# RFMC_DAC.net
KiCad netlist of a schematic drawn in Altium Designer
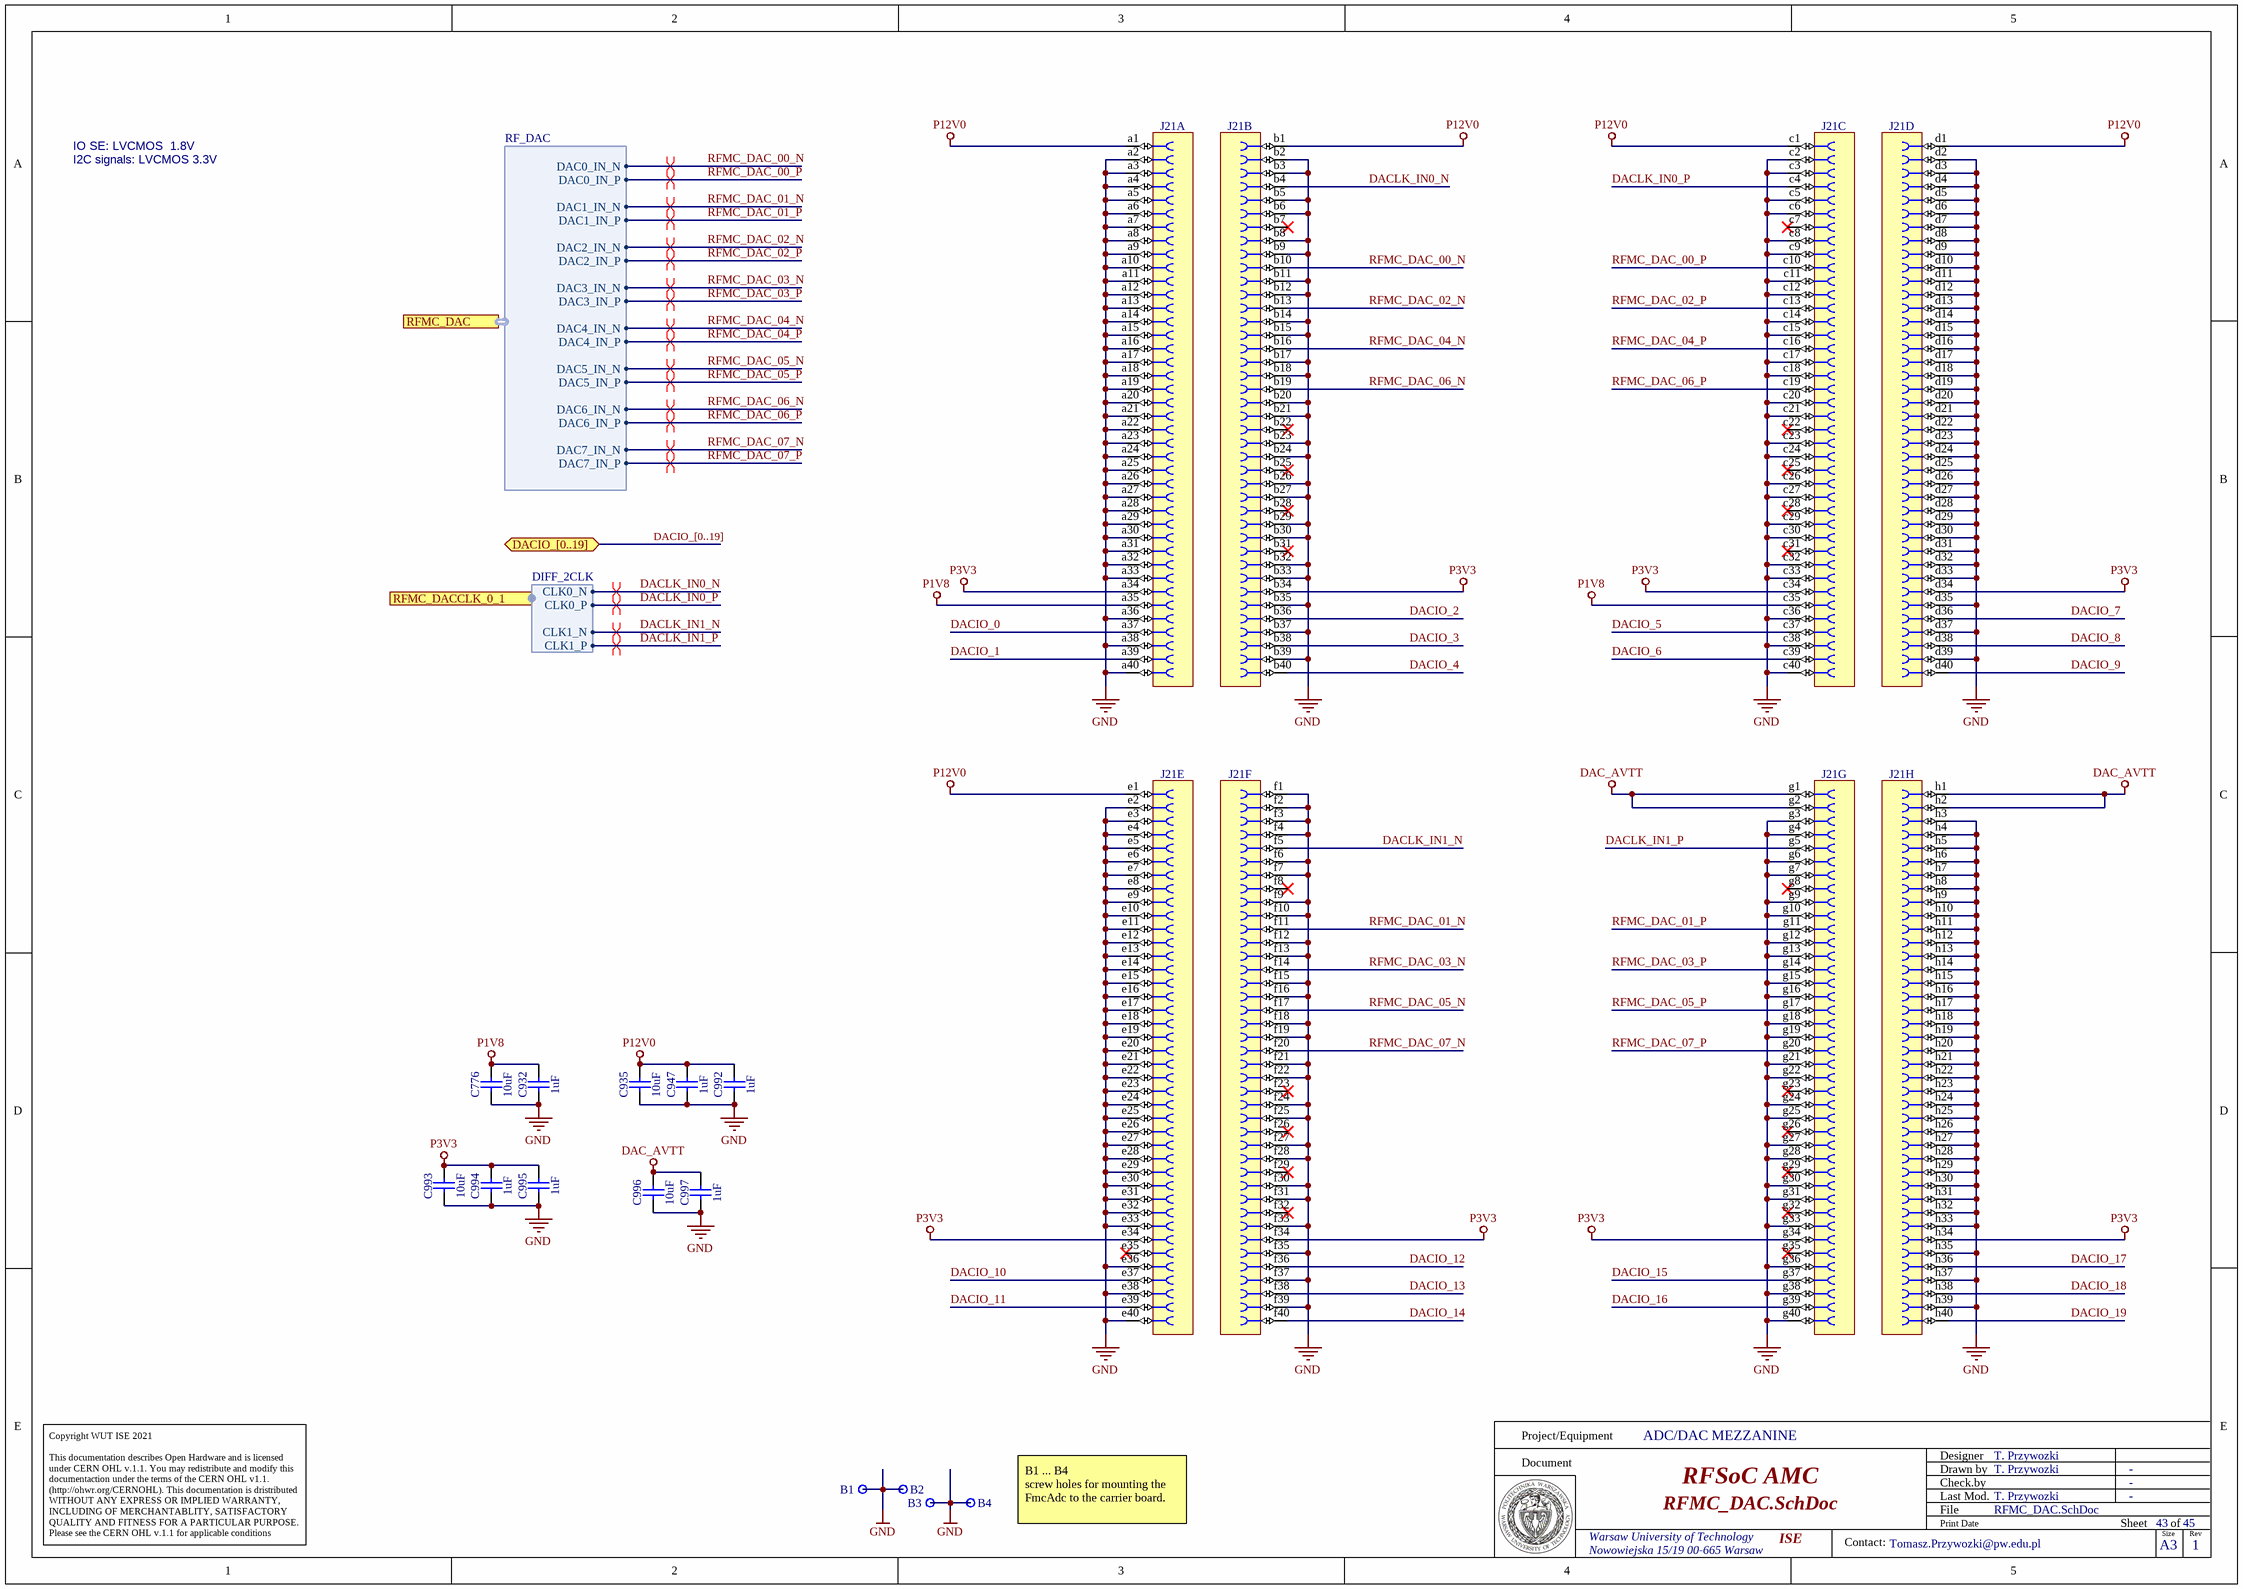
[diagram p0: RFMC_DAC.SchDoc]

(export (version "E")
  (design (tool "Eeschema 10.0.6"))
  (components
    (comp (ref "B1")
      (value "Plated Hole")
      (footprint "MTG270_500")
      (description "Single Terminal Socket")
      (fields (field (name "PART NUMBER") "PLATED_HOLE2.7_PAD5.0") (field (name "AUTHOR") "CERN DEM JMW"))
      (libsource (lib "Eletro-mechanical") (part "Single Terminal Socket"))
    )
    (comp (ref "B2")
      (value "Plated Hole")
      (footprint "MTG270_500")
      (description "Single Terminal Socket")
      (fields (field (name "PART NUMBER") "PLATED_HOLE2.7_PAD5.0") (field (name "AUTHOR") "CERN DEM JMW"))
      (libsource (lib "Eletro-mechanical") (part "Single Terminal Socket"))
    )
    (comp (ref "B3")
      (value "Plated Hole")
      (footprint "MTG270_500")
      (description "Single Terminal Socket")
      (fields (field (name "PART NUMBER") "PLATED_HOLE2.7_PAD5.0") (field (name "AUTHOR") "CERN DEM JMW"))
      (libsource (lib "Eletro-mechanical") (part "Single Terminal Socket"))
    )
    (comp (ref "B4")
      (value "Plated Hole")
      (footprint "MTG270_500")
      (description "Single Terminal Socket")
      (fields (field (name "PART NUMBER") "PLATED_HOLE2.7_PAD5.0") (field (name "AUTHOR") "CERN DEM JMW"))
      (libsource (lib "Eletro-mechanical") (part "Single Terminal Socket"))
    )
    (comp (ref "C776")
      (value "10uF")
      (footprint "CAPC1608X80N")
      (description "Non-polarised capacitor")
      (fields
        (field (name "PART NUMBER") "CC0603_10UF_10V_10%_X5R")
        (field (name "VOLTAGE") "10V")
        (field (name "AUTHOR") "CERN DEM JLC")
      )
      (libsource (lib "Capacitors") (part "Capacitor - non polarized"))
    )
    (comp (ref "C932")
      (value "1uF")
      (footprint "CAPC1005X55N")
      (description "Non-polarised capacitor")
      (fields
        (field (name "PART NUMBER") "CC0402_1UF_16V_10%_X5R")
        (field (name "VOLTAGE") "16V")
        (field (name "AUTHOR") "CERN DEM JLC")
      )
      (libsource (lib "Capacitors") (part "Capacitor - non polarized"))
    )
    (comp (ref "C935")
      (value "10uF")
      (footprint "CAPC1608X80N")
      (description "Non-polarised capacitor")
      (fields
        (field (name "PART NUMBER") "CC0603_10UF_10V_10%_X5R")
        (field (name "VOLTAGE") "10V")
        (field (name "AUTHOR") "CERN DEM JLC")
      )
      (libsource (lib "Capacitors") (part "Capacitor - non polarized"))
    )
    (comp (ref "C947")
      (value "1uF")
      (footprint "CAPC1005X55N")
      (description "Non-polarised capacitor")
      (fields
        (field (name "PART NUMBER") "CC0402_1UF_16V_10%_X5R")
        (field (name "VOLTAGE") "16V")
        (field (name "AUTHOR") "CERN DEM JLC")
      )
      (libsource (lib "Capacitors") (part "Capacitor - non polarized"))
    )
    (comp (ref "C992")
      (value "1uF")
      (footprint "CAPC1005X55N")
      (description "Non-polarised capacitor")
      (fields
        (field (name "PART NUMBER") "CC0402_1UF_16V_10%_X5R")
        (field (name "VOLTAGE") "16V")
        (field (name "AUTHOR") "CERN DEM JLC")
      )
      (libsource (lib "Capacitors") (part "Capacitor - non polarized"))
    )
    (comp (ref "C993")
      (value "10uF")
      (footprint "CAPC1608X80N")
      (description "Non-polarised capacitor")
      (fields
        (field (name "PART NUMBER") "CC0603_10UF_10V_10%_X5R")
        (field (name "VOLTAGE") "10V")
        (field (name "AUTHOR") "CERN DEM JLC")
      )
      (libsource (lib "Capacitors") (part "Capacitor - non polarized"))
    )
    (comp (ref "C994")
      (value "1uF")
      (footprint "CAPC1005X55N")
      (description "Non-polarised capacitor")
      (fields
        (field (name "PART NUMBER") "CC0402_1UF_16V_10%_X5R")
        (field (name "VOLTAGE") "16V")
        (field (name "AUTHOR") "CERN DEM JLC")
      )
      (libsource (lib "Capacitors") (part "Capacitor - non polarized"))
    )
    (comp (ref "C995")
      (value "1uF")
      (footprint "CAPC1005X55N")
      (description "Non-polarised capacitor")
      (fields
        (field (name "PART NUMBER") "CC0402_1UF_16V_10%_X5R")
        (field (name "VOLTAGE") "16V")
        (field (name "AUTHOR") "CERN DEM JLC")
      )
      (libsource (lib "Capacitors") (part "Capacitor - non polarized"))
    )
    (comp (ref "C996")
      (value "10uF")
      (footprint "CAPC1608X80N")
      (description "Non-polarised capacitor")
      (fields
        (field (name "PART NUMBER") "CC0603_10UF_10V_10%_X5R")
        (field (name "VOLTAGE") "10V")
        (field (name "AUTHOR") "CERN DEM JLC")
      )
      (libsource (lib "Capacitors") (part "Capacitor - non polarized"))
    )
    (comp (ref "C997")
      (value "1uF")
      (footprint "CAPC1005X55N")
      (description "Non-polarised capacitor")
      (fields
        (field (name "PART NUMBER") "CC0402_1UF_16V_10%_X5R")
        (field (name "VOLTAGE") "16V")
        (field (name "AUTHOR") "CERN DEM JLC")
      )
      (libsource (lib "Capacitors") (part "Capacitor - non polarized"))
    )
    (comp (ref "J21")
      (value "~")
      (footprint "SAMTEC_LPAF-40-03.0-S-08")
      (description "Connector 320 Female contacts in 8 row abcdef")
      (fields
        (field (name "PART NUMBER") "SAMTEC_LPAF-40-03.0-S-08-2-K")
        (field (name "MANUFACTURER") "SAMTEC")
        (field (name "AUTHOR") "CERN DEM BC")
      )
      (libsource (lib "Connectors") (part "Connector 320 Female (8x40) (abcdefgh)"))
    )
  )
  (nets
    (net (code "3") (name "/DACIO_0") (class "Default")
      (node (ref "J21") (pin "a37") (pinfunction "a37_a37") (pintype "bidirectional"))
    )
    (net (code "4") (name "/DACIO_1") (class "Default")
      (node (ref "J21") (pin "a39") (pinfunction "a39_a39") (pintype "bidirectional"))
    )
    (net (code "5") (name "/DACIO_2") (class "Default")
      (node (ref "J21") (pin "b36") (pinfunction "b36_b36") (pintype "bidirectional"))
    )
    (net (code "6") (name "/DACIO_3") (class "Default")
      (node (ref "J21") (pin "b38") (pinfunction "b38_b38") (pintype "bidirectional"))
    )
    (net (code "7") (name "/DACIO_4") (class "Default")
      (node (ref "J21") (pin "b40") (pinfunction "b40_b40") (pintype "bidirectional"))
    )
    (net (code "8") (name "/DACIO_5") (class "Default")
      (node (ref "J21") (pin "c37") (pinfunction "c37_c37") (pintype "bidirectional"))
    )
    (net (code "9") (name "/DACIO_6") (class "Default")
      (node (ref "J21") (pin "c39") (pinfunction "c39_c39") (pintype "bidirectional"))
    )
    (net (code "10") (name "/DACIO_7") (class "Default")
      (node (ref "J21") (pin "d36") (pinfunction "d36_d36") (pintype "bidirectional"))
    )
    (net (code "11") (name "/DACIO_8") (class "Default")
      (node (ref "J21") (pin "d38") (pinfunction "d38_d38") (pintype "bidirectional"))
    )
    (net (code "12") (name "/DACIO_9") (class "Default")
      (node (ref "J21") (pin "d40") (pinfunction "d40_d40") (pintype "bidirectional"))
    )
    (net (code "13") (name "/DACIO_10") (class "Default")
      (node (ref "J21") (pin "e37") (pinfunction "e37_e37") (pintype "bidirectional"))
    )
    (net (code "14") (name "/DACIO_11") (class "Default")
      (node (ref "J21") (pin "e39") (pinfunction "e39_e39") (pintype "bidirectional"))
    )
    (net (code "15") (name "/DACIO_12") (class "Default")
      (node (ref "J21") (pin "f36") (pinfunction "f36_f36") (pintype "bidirectional"))
    )
    (net (code "16") (name "/DACIO_13") (class "Default")
      (node (ref "J21") (pin "f38") (pinfunction "f38_f38") (pintype "bidirectional"))
    )
    (net (code "17") (name "/DACIO_14") (class "Default")
      (node (ref "J21") (pin "f40") (pinfunction "f40_f40") (pintype "bidirectional"))
    )
    (net (code "18") (name "/DACIO_15") (class "Default")
      (node (ref "J21") (pin "g37") (pinfunction "g37_g37") (pintype "bidirectional"))
    )
    (net (code "19") (name "/DACIO_16") (class "Default")
      (node (ref "J21") (pin "g39") (pinfunction "g39_g39") (pintype "bidirectional"))
    )
    (net (code "20") (name "/DACIO_17") (class "Default")
      (node (ref "J21") (pin "h36") (pinfunction "h36_h36") (pintype "bidirectional"))
    )
    (net (code "21") (name "/DACIO_18") (class "Default")
      (node (ref "J21") (pin "h38") (pinfunction "h38_h38") (pintype "bidirectional"))
    )
    (net (code "22") (name "/DACIO_19") (class "Default")
      (node (ref "J21") (pin "h40") (pinfunction "h40_h40") (pintype "bidirectional"))
    )
    (net (code "24") (name "/DACLK_IN0_N") (class "Default")
      (node (ref "J21") (pin "b4") (pinfunction "b4_b4") (pintype "bidirectional"))
    )
    (net (code "25") (name "/DACLK_IN0_P") (class "Default")
      (node (ref "J21") (pin "c4") (pinfunction "c4_c4") (pintype "bidirectional"))
    )
    (net (code "26") (name "/DACLK_IN1_N") (class "Default")
      (node (ref "J21") (pin "f5") (pinfunction "f5_f5") (pintype "bidirectional"))
    )
    (net (code "27") (name "/DACLK_IN1_P") (class "Default")
      (node (ref "J21") (pin "g5") (pinfunction "g5_g5") (pintype "bidirectional"))
    )
    (net (code "28") (name "/RFMC_DAC_00_N") (class "Default")
      (node (ref "J21") (pin "b10") (pinfunction "b10_b10") (pintype "bidirectional"))
    )
    (net (code "29") (name "/RFMC_DAC_00_P") (class "Default")
      (node (ref "J21") (pin "c10") (pinfunction "c10_c10") (pintype "bidirectional"))
    )
    (net (code "30") (name "/RFMC_DAC_01_N") (class "Default")
      (node (ref "J21") (pin "f11") (pinfunction "f11_f11") (pintype "bidirectional"))
    )
    (net (code "31") (name "/RFMC_DAC_01_P") (class "Default")
      (node (ref "J21") (pin "g11") (pinfunction "g11_g11") (pintype "bidirectional"))
    )
    (net (code "32") (name "/RFMC_DAC_02_N") (class "Default")
      (node (ref "J21") (pin "b13") (pinfunction "b13_b13") (pintype "bidirectional"))
    )
    (net (code "33") (name "/RFMC_DAC_02_P") (class "Default")
      (node (ref "J21") (pin "c13") (pinfunction "c13_c13") (pintype "bidirectional"))
    )
    (net (code "34") (name "/RFMC_DAC_03_N") (class "Default")
      (node (ref "J21") (pin "f14") (pinfunction "f14_f14") (pintype "bidirectional"))
    )
    (net (code "35") (name "/RFMC_DAC_03_P") (class "Default")
      (node (ref "J21") (pin "g14") (pinfunction "g14_g14") (pintype "bidirectional"))
    )
    (net (code "36") (name "/RFMC_DAC_04_N") (class "Default")
      (node (ref "J21") (pin "b16") (pinfunction "b16_b16") (pintype "bidirectional"))
    )
    (net (code "37") (name "/RFMC_DAC_04_P") (class "Default")
      (node (ref "J21") (pin "c16") (pinfunction "c16_c16") (pintype "bidirectional"))
    )
    (net (code "38") (name "/RFMC_DAC_05_N") (class "Default")
      (node (ref "J21") (pin "f17") (pinfunction "f17_f17") (pintype "bidirectional"))
    )
    (net (code "39") (name "/RFMC_DAC_05_P") (class "Default")
      (node (ref "J21") (pin "g17") (pinfunction "g17_g17") (pintype "bidirectional"))
    )
    (net (code "40") (name "/RFMC_DAC_06_N") (class "Default")
      (node (ref "J21") (pin "b19") (pinfunction "b19_b19") (pintype "bidirectional"))
    )
    (net (code "41") (name "/RFMC_DAC_06_P") (class "Default")
      (node (ref "J21") (pin "c19") (pinfunction "c19_c19") (pintype "bidirectional"))
    )
    (net (code "42") (name "/RFMC_DAC_07_N") (class "Default")
      (node (ref "J21") (pin "f20") (pinfunction "f20_f20") (pintype "bidirectional"))
    )
    (net (code "43") (name "/RFMC_DAC_07_P") (class "Default")
      (node (ref "J21") (pin "g20") (pinfunction "g20_g20") (pintype "bidirectional"))
    )
    (net (code "46") (name "DAC_AVTT") (class "Default")
      (node (ref "C996") (pin "2") (pinfunction "2_2") (pintype "passive"))
      (node (ref "C997") (pin "1") (pinfunction "1_1") (pintype "passive"))
      (node (ref "J21") (pin "g1") (pinfunction "g1_g1") (pintype "bidirectional"))
      (node (ref "J21") (pin "g2") (pinfunction "g2_g2") (pintype "bidirectional"))
      (node (ref "J21") (pin "h1") (pinfunction "h1_h1") (pintype "bidirectional"))
      (node (ref "J21") (pin "h2") (pinfunction "h2_h2") (pintype "bidirectional"))
    )
    (net (code "47") (name "GND") (class "Default")
      (node (ref "B1") (pin "1") (pinfunction "1_1") (pintype "bidirectional"))
      (node (ref "B2") (pin "1") (pinfunction "1_1") (pintype "bidirectional"))
      (node (ref "B3") (pin "1") (pinfunction "1_1") (pintype "bidirectional"))
      (node (ref "B4") (pin "1") (pinfunction "1_1") (pintype "bidirectional"))
      (node (ref "C776") (pin "1") (pinfunction "1_1") (pintype "passive"))
      (node (ref "C932") (pin "2") (pinfunction "2_2") (pintype "passive"))
      (node (ref "C935") (pin "1") (pinfunction "1_1") (pintype "passive"))
      (node (ref "C947") (pin "2") (pinfunction "2_2") (pintype "passive"))
      (node (ref "C992") (pin "2") (pinfunction "2_2") (pintype "passive"))
      (node (ref "C993") (pin "1") (pinfunction "1_1") (pintype "passive"))
      (node (ref "C994") (pin "2") (pinfunction "2_2") (pintype "passive"))
      (node (ref "C995") (pin "2") (pinfunction "2_2") (pintype "passive"))
      (node (ref "C996") (pin "1") (pinfunction "1_1") (pintype "passive"))
      (node (ref "C997") (pin "2") (pinfunction "2_2") (pintype "passive"))
      (node (ref "J21") (pin "a10") (pinfunction "a10_a10") (pintype "bidirectional"))
      (node (ref "J21") (pin "a11") (pinfunction "a11_a11") (pintype "bidirectional"))
      (node (ref "J21") (pin "a12") (pinfunction "a12_a12") (pintype "bidirectional"))
      (node (ref "J21") (pin "a13") (pinfunction "a13_a13") (pintype "bidirectional"))
      (node (ref "J21") (pin "a14") (pinfunction "a14_a14") (pintype "bidirectional"))
      (node (ref "J21") (pin "a15") (pinfunction "a15_a15") (pintype "bidirectional"))
      (node (ref "J21") (pin "a16") (pinfunction "a16_a16") (pintype "bidirectional"))
      (node (ref "J21") (pin "a17") (pinfunction "a17_a17") (pintype "bidirectional"))
      (node (ref "J21") (pin "a18") (pinfunction "a18_a18") (pintype "bidirectional"))
      (node (ref "J21") (pin "a19") (pinfunction "a19_a19") (pintype "bidirectional"))
      (node (ref "J21") (pin "a2") (pinfunction "a2_a2") (pintype "bidirectional"))
      (node (ref "J21") (pin "a20") (pinfunction "a20_a20") (pintype "bidirectional"))
      (node (ref "J21") (pin "a21") (pinfunction "a21_a21") (pintype "bidirectional"))
      (node (ref "J21") (pin "a22") (pinfunction "a22_a22") (pintype "bidirectional"))
      (node (ref "J21") (pin "a23") (pinfunction "a23_a23") (pintype "bidirectional"))
      (node (ref "J21") (pin "a24") (pinfunction "a24_a24") (pintype "bidirectional"))
      (node (ref "J21") (pin "a25") (pinfunction "a25_a25") (pintype "bidirectional"))
      (node (ref "J21") (pin "a26") (pinfunction "a26_a26") (pintype "bidirectional"))
      (node (ref "J21") (pin "a27") (pinfunction "a27_a27") (pintype "bidirectional"))
      (node (ref "J21") (pin "a28") (pinfunction "a28_a28") (pintype "bidirectional"))
      (node (ref "J21") (pin "a29") (pinfunction "a29_a29") (pintype "bidirectional"))
      (node (ref "J21") (pin "a3") (pinfunction "a3_a3") (pintype "bidirectional"))
      (node (ref "J21") (pin "a30") (pinfunction "a30_a30") (pintype "bidirectional"))
      (node (ref "J21") (pin "a31") (pinfunction "a31_a31") (pintype "bidirectional"))
      (node (ref "J21") (pin "a32") (pinfunction "a32_a32") (pintype "bidirectional"))
      (node (ref "J21") (pin "a33") (pinfunction "a33_a33") (pintype "bidirectional"))
      (node (ref "J21") (pin "a36") (pinfunction "a36_a36") (pintype "bidirectional"))
      (node (ref "J21") (pin "a38") (pinfunction "a38_a38") (pintype "bidirectional"))
      (node (ref "J21") (pin "a4") (pinfunction "a4_a4") (pintype "bidirectional"))
      (node (ref "J21") (pin "a40") (pinfunction "a40_a40") (pintype "bidirectional"))
      (node (ref "J21") (pin "a5") (pinfunction "a5_a5") (pintype "bidirectional"))
      (node (ref "J21") (pin "a6") (pinfunction "a6_a6") (pintype "bidirectional"))
      (node (ref "J21") (pin "a7") (pinfunction "a7_a7") (pintype "bidirectional"))
      (node (ref "J21") (pin "a8") (pinfunction "a8_a8") (pintype "bidirectional"))
      (node (ref "J21") (pin "a9") (pinfunction "a9_a9") (pintype "bidirectional"))
      (node (ref "J21") (pin "b11") (pinfunction "b11_b11") (pintype "bidirectional"))
      (node (ref "J21") (pin "b12") (pinfunction "b12_b12") (pintype "bidirectional"))
      (node (ref "J21") (pin "b14") (pinfunction "b14_b14") (pintype "bidirectional"))
      (node (ref "J21") (pin "b15") (pinfunction "b15_b15") (pintype "bidirectional"))
      (node (ref "J21") (pin "b17") (pinfunction "b17_b17") (pintype "bidirectional"))
      (node (ref "J21") (pin "b18") (pinfunction "b18_b18") (pintype "bidirectional"))
      (node (ref "J21") (pin "b2") (pinfunction "b2_b2") (pintype "bidirectional"))
      (node (ref "J21") (pin "b20") (pinfunction "b20_b20") (pintype "bidirectional"))
      (node (ref "J21") (pin "b21") (pinfunction "b21_b21") (pintype "bidirectional"))
      (node (ref "J21") (pin "b23") (pinfunction "b23_b23") (pintype "bidirectional"))
      (node (ref "J21") (pin "b24") (pinfunction "b24_b24") (pintype "bidirectional"))
      (node (ref "J21") (pin "b26") (pinfunction "b26_b26") (pintype "bidirectional"))
      (node (ref "J21") (pin "b27") (pinfunction "b27_b27") (pintype "bidirectional"))
      (node (ref "J21") (pin "b29") (pinfunction "b29_b29") (pintype "bidirectional"))
      (node (ref "J21") (pin "b3") (pinfunction "b3_b3") (pintype "bidirectional"))
      (node (ref "J21") (pin "b30") (pinfunction "b30_b30") (pintype "bidirectional"))
      (node (ref "J21") (pin "b32") (pinfunction "b32_b32") (pintype "bidirectional"))
      (node (ref "J21") (pin "b33") (pinfunction "b33_b33") (pintype "bidirectional"))
      (node (ref "J21") (pin "b35") (pinfunction "b35_b35") (pintype "bidirectional"))
      (node (ref "J21") (pin "b37") (pinfunction "b37_b37") (pintype "bidirectional"))
      (node (ref "J21") (pin "b39") (pinfunction "b39_b39") (pintype "bidirectional"))
      (node (ref "J21") (pin "b5") (pinfunction "b5_b5") (pintype "bidirectional"))
      (node (ref "J21") (pin "b6") (pinfunction "b6_b6") (pintype "bidirectional"))
      (node (ref "J21") (pin "b8") (pinfunction "b8_b8") (pintype "bidirectional"))
      (node (ref "J21") (pin "b9") (pinfunction "b9_b9") (pintype "bidirectional"))
      (node (ref "J21") (pin "c11") (pinfunction "c11_c11") (pintype "bidirectional"))
      (node (ref "J21") (pin "c12") (pinfunction "c12_c12") (pintype "bidirectional"))
      (node (ref "J21") (pin "c14") (pinfunction "c14_c14") (pintype "bidirectional"))
      (node (ref "J21") (pin "c15") (pinfunction "c15_c15") (pintype "bidirectional"))
      (node (ref "J21") (pin "c17") (pinfunction "c17_c17") (pintype "bidirectional"))
      (node (ref "J21") (pin "c18") (pinfunction "c18_c18") (pintype "bidirectional"))
      (node (ref "J21") (pin "c2") (pinfunction "c2_c2") (pintype "bidirectional"))
      (node (ref "J21") (pin "c20") (pinfunction "c20_c20") (pintype "bidirectional"))
      (node (ref "J21") (pin "c21") (pinfunction "c21_c21") (pintype "bidirectional"))
      (node (ref "J21") (pin "c23") (pinfunction "c23_c23") (pintype "bidirectional"))
      (node (ref "J21") (pin "c24") (pinfunction "c24_c24") (pintype "bidirectional"))
      (node (ref "J21") (pin "c26") (pinfunction "c26_c26") (pintype "bidirectional"))
      (node (ref "J21") (pin "c27") (pinfunction "c27_c27") (pintype "bidirectional"))
      (node (ref "J21") (pin "c29") (pinfunction "c29_c29") (pintype "bidirectional"))
      (node (ref "J21") (pin "c3") (pinfunction "c3_c3") (pintype "bidirectional"))
      (node (ref "J21") (pin "c30") (pinfunction "c30_c30") (pintype "bidirectional"))
      (node (ref "J21") (pin "c32") (pinfunction "c32_c32") (pintype "bidirectional"))
      (node (ref "J21") (pin "c33") (pinfunction "c33_c33") (pintype "bidirectional"))
      (node (ref "J21") (pin "c36") (pinfunction "c36_c36") (pintype "bidirectional"))
      (node (ref "J21") (pin "c38") (pinfunction "c38_c38") (pintype "bidirectional"))
      (node (ref "J21") (pin "c40") (pinfunction "c40_c40") (pintype "bidirectional"))
      (node (ref "J21") (pin "c5") (pinfunction "c5_c5") (pintype "bidirectional"))
      (node (ref "J21") (pin "c6") (pinfunction "c6_c6") (pintype "bidirectional"))
      (node (ref "J21") (pin "c8") (pinfunction "c8_c8") (pintype "bidirectional"))
      (node (ref "J21") (pin "c9") (pinfunction "c9_c9") (pintype "bidirectional"))
      (node (ref "J21") (pin "d10") (pinfunction "d10_d10") (pintype "bidirectional"))
      (node (ref "J21") (pin "d11") (pinfunction "d11_d11") (pintype "bidirectional"))
      (node (ref "J21") (pin "d12") (pinfunction "d12_d12") (pintype "bidirectional"))
      (node (ref "J21") (pin "d13") (pinfunction "d13_d13") (pintype "bidirectional"))
      (node (ref "J21") (pin "d14") (pinfunction "d14_d14") (pintype "bidirectional"))
      (node (ref "J21") (pin "d15") (pinfunction "d15_d15") (pintype "bidirectional"))
      (node (ref "J21") (pin "d16") (pinfunction "d16_d16") (pintype "bidirectional"))
      (node (ref "J21") (pin "d17") (pinfunction "d17_d17") (pintype "bidirectional"))
      (node (ref "J21") (pin "d18") (pinfunction "d18_d18") (pintype "bidirectional"))
      (node (ref "J21") (pin "d19") (pinfunction "d19_d19") (pintype "bidirectional"))
      (node (ref "J21") (pin "d2") (pinfunction "d2_d2") (pintype "bidirectional"))
      (node (ref "J21") (pin "d20") (pinfunction "d20_d20") (pintype "bidirectional"))
      (node (ref "J21") (pin "d21") (pinfunction "d21_d21") (pintype "bidirectional"))
      (node (ref "J21") (pin "d22") (pinfunction "d22_d22") (pintype "bidirectional"))
      (node (ref "J21") (pin "d23") (pinfunction "d23_d23") (pintype "bidirectional"))
      (node (ref "J21") (pin "d24") (pinfunction "d24_d24") (pintype "bidirectional"))
      (node (ref "J21") (pin "d25") (pinfunction "d25_d25") (pintype "bidirectional"))
      (node (ref "J21") (pin "d26") (pinfunction "d26_d26") (pintype "bidirectional"))
      (node (ref "J21") (pin "d27") (pinfunction "d27_d27") (pintype "bidirectional"))
      (node (ref "J21") (pin "d28") (pinfunction "d28_d28") (pintype "bidirectional"))
      (node (ref "J21") (pin "d29") (pinfunction "d29_d29") (pintype "bidirectional"))
      (node (ref "J21") (pin "d3") (pinfunction "d3_d3") (pintype "bidirectional"))
      (node (ref "J21") (pin "d30") (pinfunction "d30_d30") (pintype "bidirectional"))
      (node (ref "J21") (pin "d31") (pinfunction "d31_d31") (pintype "bidirectional"))
      (node (ref "J21") (pin "d32") (pinfunction "d32_d32") (pintype "bidirectional"))
      (node (ref "J21") (pin "d33") (pinfunction "d33_d33") (pintype "bidirectional"))
      (node (ref "J21") (pin "d35") (pinfunction "d35_d35") (pintype "bidirectional"))
      (node (ref "J21") (pin "d37") (pinfunction "d37_d37") (pintype "bidirectional"))
      (node (ref "J21") (pin "d39") (pinfunction "d39_d39") (pintype "bidirectional"))
      (node (ref "J21") (pin "d4") (pinfunction "d4_d4") (pintype "bidirectional"))
      (node (ref "J21") (pin "d5") (pinfunction "d5_d5") (pintype "bidirectional"))
      (node (ref "J21") (pin "d6") (pinfunction "d6_d6") (pintype "bidirectional"))
      (node (ref "J21") (pin "d7") (pinfunction "d7_d7") (pintype "bidirectional"))
      (node (ref "J21") (pin "d8") (pinfunction "d8_d8") (pintype "bidirectional"))
      (node (ref "J21") (pin "d9") (pinfunction "d9_d9") (pintype "bidirectional"))
      (node (ref "J21") (pin "e10") (pinfunction "e10_e10") (pintype "bidirectional"))
      (node (ref "J21") (pin "e11") (pinfunction "e11_e11") (pintype "bidirectional"))
      (node (ref "J21") (pin "e12") (pinfunction "e12_e12") (pintype "bidirectional"))
      (node (ref "J21") (pin "e13") (pinfunction "e13_e13") (pintype "bidirectional"))
      (node (ref "J21") (pin "e14") (pinfunction "e14_e14") (pintype "bidirectional"))
      (node (ref "J21") (pin "e15") (pinfunction "e15_e15") (pintype "bidirectional"))
      (node (ref "J21") (pin "e16") (pinfunction "e16_e16") (pintype "bidirectional"))
      (node (ref "J21") (pin "e17") (pinfunction "e17_e17") (pintype "bidirectional"))
      (node (ref "J21") (pin "e18") (pinfunction "e18_e18") (pintype "bidirectional"))
      (node (ref "J21") (pin "e19") (pinfunction "e19_e19") (pintype "bidirectional"))
      (node (ref "J21") (pin "e2") (pinfunction "e2_e2") (pintype "bidirectional"))
      (node (ref "J21") (pin "e20") (pinfunction "e20_e20") (pintype "bidirectional"))
      (node (ref "J21") (pin "e21") (pinfunction "e21_e21") (pintype "bidirectional"))
      (node (ref "J21") (pin "e22") (pinfunction "e22_e22") (pintype "bidirectional"))
      (node (ref "J21") (pin "e23") (pinfunction "e23_e23") (pintype "bidirectional"))
      (node (ref "J21") (pin "e24") (pinfunction "e24_e24") (pintype "bidirectional"))
      (node (ref "J21") (pin "e25") (pinfunction "e25_e25") (pintype "bidirectional"))
      (node (ref "J21") (pin "e26") (pinfunction "e26_e26") (pintype "bidirectional"))
      (node (ref "J21") (pin "e27") (pinfunction "e27_e27") (pintype "bidirectional"))
      (node (ref "J21") (pin "e28") (pinfunction "e28_e28") (pintype "bidirectional"))
      (node (ref "J21") (pin "e29") (pinfunction "e29_e29") (pintype "bidirectional"))
      (node (ref "J21") (pin "e3") (pinfunction "e3_e3") (pintype "bidirectional"))
      (node (ref "J21") (pin "e30") (pinfunction "e30_e30") (pintype "bidirectional"))
      (node (ref "J21") (pin "e31") (pinfunction "e31_e31") (pintype "bidirectional"))
      (node (ref "J21") (pin "e32") (pinfunction "e32_e32") (pintype "bidirectional"))
      (node (ref "J21") (pin "e33") (pinfunction "e33_e33") (pintype "bidirectional"))
      (node (ref "J21") (pin "e36") (pinfunction "e36_e36") (pintype "bidirectional"))
      (node (ref "J21") (pin "e38") (pinfunction "e38_e38") (pintype "bidirectional"))
      (node (ref "J21") (pin "e4") (pinfunction "e4_e4") (pintype "bidirectional"))
      (node (ref "J21") (pin "e40") (pinfunction "e40_e40") (pintype "bidirectional"))
      (node (ref "J21") (pin "e5") (pinfunction "e5_e5") (pintype "bidirectional"))
      (node (ref "J21") (pin "e6") (pinfunction "e6_e6") (pintype "bidirectional"))
      (node (ref "J21") (pin "e7") (pinfunction "e7_e7") (pintype "bidirectional"))
      (node (ref "J21") (pin "e8") (pinfunction "e8_e8") (pintype "bidirectional"))
      (node (ref "J21") (pin "e9") (pinfunction "e9_e9") (pintype "bidirectional"))
      (node (ref "J21") (pin "f1") (pinfunction "f1_f1") (pintype "bidirectional"))
      (node (ref "J21") (pin "f10") (pinfunction "f10_f10") (pintype "bidirectional"))
      (node (ref "J21") (pin "f12") (pinfunction "f12_f12") (pintype "bidirectional"))
      (node (ref "J21") (pin "f13") (pinfunction "f13_f13") (pintype "bidirectional"))
      (node (ref "J21") (pin "f15") (pinfunction "f15_f15") (pintype "bidirectional"))
      (node (ref "J21") (pin "f16") (pinfunction "f16_f16") (pintype "bidirectional"))
      (node (ref "J21") (pin "f18") (pinfunction "f18_f18") (pintype "bidirectional"))
      (node (ref "J21") (pin "f19") (pinfunction "f19_f19") (pintype "bidirectional"))
      (node (ref "J21") (pin "f2") (pinfunction "f2_f2") (pintype "bidirectional"))
      (node (ref "J21") (pin "f21") (pinfunction "f21_f21") (pintype "bidirectional"))
      (node (ref "J21") (pin "f22") (pinfunction "f22_f22") (pintype "bidirectional"))
      (node (ref "J21") (pin "f24") (pinfunction "f24_f24") (pintype "bidirectional"))
      (node (ref "J21") (pin "f25") (pinfunction "f25_f25") (pintype "bidirectional"))
      (node (ref "J21") (pin "f27") (pinfunction "f27_f27") (pintype "bidirectional"))
      (node (ref "J21") (pin "f28") (pinfunction "f28_f28") (pintype "bidirectional"))
      (node (ref "J21") (pin "f3") (pinfunction "f3_f3") (pintype "bidirectional"))
      (node (ref "J21") (pin "f30") (pinfunction "f30_f30") (pintype "bidirectional"))
      (node (ref "J21") (pin "f31") (pinfunction "f31_f31") (pintype "bidirectional"))
      (node (ref "J21") (pin "f33") (pinfunction "f33_f33") (pintype "bidirectional"))
      (node (ref "J21") (pin "f35") (pinfunction "f35_f35") (pintype "bidirectional"))
      (node (ref "J21") (pin "f37") (pinfunction "f37_f37") (pintype "bidirectional"))
      (node (ref "J21") (pin "f39") (pinfunction "f39_f39") (pintype "bidirectional"))
      (node (ref "J21") (pin "f4") (pinfunction "f4_f4") (pintype "bidirectional"))
      (node (ref "J21") (pin "f6") (pinfunction "f6_f6") (pintype "bidirectional"))
      (node (ref "J21") (pin "f7") (pinfunction "f7_f7") (pintype "bidirectional"))
      (node (ref "J21") (pin "f9") (pinfunction "f9_f9") (pintype "bidirectional"))
      (node (ref "J21") (pin "g10") (pinfunction "g10_g10") (pintype "bidirectional"))
      (node (ref "J21") (pin "g12") (pinfunction "g12_g12") (pintype "bidirectional"))
      (node (ref "J21") (pin "g13") (pinfunction "g13_g13") (pintype "bidirectional"))
      (node (ref "J21") (pin "g15") (pinfunction "g15_g15") (pintype "bidirectional"))
      (node (ref "J21") (pin "g16") (pinfunction "g16_g16") (pintype "bidirectional"))
      (node (ref "J21") (pin "g18") (pinfunction "g18_g18") (pintype "bidirectional"))
      (node (ref "J21") (pin "g19") (pinfunction "g19_g19") (pintype "bidirectional"))
      (node (ref "J21") (pin "g21") (pinfunction "g21_g21") (pintype "bidirectional"))
      (node (ref "J21") (pin "g22") (pinfunction "g22_g22") (pintype "bidirectional"))
      (node (ref "J21") (pin "g24") (pinfunction "g24_g24") (pintype "bidirectional"))
      (node (ref "J21") (pin "g25") (pinfunction "g25_g25") (pintype "bidirectional"))
      (node (ref "J21") (pin "g27") (pinfunction "g27_g27") (pintype "bidirectional"))
      (node (ref "J21") (pin "g28") (pinfunction "g28_g28") (pintype "bidirectional"))
      (node (ref "J21") (pin "g3") (pinfunction "g3_g3") (pintype "bidirectional"))
      (node (ref "J21") (pin "g30") (pinfunction "g30_g30") (pintype "bidirectional"))
      (node (ref "J21") (pin "g31") (pinfunction "g31_g31") (pintype "bidirectional"))
      (node (ref "J21") (pin "g33") (pinfunction "g33_g33") (pintype "bidirectional"))
      (node (ref "J21") (pin "g36") (pinfunction "g36_g36") (pintype "bidirectional"))
      (node (ref "J21") (pin "g38") (pinfunction "g38_g38") (pintype "bidirectional"))
      (node (ref "J21") (pin "g4") (pinfunction "g4_g4") (pintype "bidirectional"))
      (node (ref "J21") (pin "g40") (pinfunction "g40_g40") (pintype "bidirectional"))
      (node (ref "J21") (pin "g6") (pinfunction "g6_g6") (pintype "bidirectional"))
      (node (ref "J21") (pin "g7") (pinfunction "g7_g7") (pintype "bidirectional"))
      (node (ref "J21") (pin "g9") (pinfunction "g9_g9") (pintype "bidirectional"))
      (node (ref "J21") (pin "h10") (pinfunction "h10_h10") (pintype "bidirectional"))
      (node (ref "J21") (pin "h11") (pinfunction "h11_h11") (pintype "bidirectional"))
      (node (ref "J21") (pin "h12") (pinfunction "h12_h12") (pintype "bidirectional"))
      (node (ref "J21") (pin "h13") (pinfunction "h13_h13") (pintype "bidirectional"))
      (node (ref "J21") (pin "h14") (pinfunction "h14_h14") (pintype "bidirectional"))
      (node (ref "J21") (pin "h15") (pinfunction "h15_h15") (pintype "bidirectional"))
      (node (ref "J21") (pin "h16") (pinfunction "h16_h16") (pintype "bidirectional"))
      (node (ref "J21") (pin "h17") (pinfunction "h17_h17") (pintype "bidirectional"))
      (node (ref "J21") (pin "h18") (pinfunction "h18_h18") (pintype "bidirectional"))
      (node (ref "J21") (pin "h19") (pinfunction "h19_h19") (pintype "bidirectional"))
      (node (ref "J21") (pin "h20") (pinfunction "h20_h20") (pintype "bidirectional"))
      (node (ref "J21") (pin "h21") (pinfunction "h21_h21") (pintype "bidirectional"))
      (node (ref "J21") (pin "h22") (pinfunction "h22_h22") (pintype "bidirectional"))
      (node (ref "J21") (pin "h23") (pinfunction "h23_h23") (pintype "bidirectional"))
      (node (ref "J21") (pin "h24") (pinfunction "h24_h24") (pintype "bidirectional"))
      (node (ref "J21") (pin "h25") (pinfunction "h25_h25") (pintype "bidirectional"))
      (node (ref "J21") (pin "h26") (pinfunction "h26_h26") (pintype "bidirectional"))
      (node (ref "J21") (pin "h27") (pinfunction "h27_h27") (pintype "bidirectional"))
      (node (ref "J21") (pin "h28") (pinfunction "h28_h28") (pintype "bidirectional"))
      (node (ref "J21") (pin "h29") (pinfunction "h29_h29") (pintype "bidirectional"))
      (node (ref "J21") (pin "h3") (pinfunction "h3_h3") (pintype "bidirectional"))
      (node (ref "J21") (pin "h30") (pinfunction "h30_h30") (pintype "bidirectional"))
      (node (ref "J21") (pin "h31") (pinfunction "h31_h31") (pintype "bidirectional"))
      (node (ref "J21") (pin "h32") (pinfunction "h32_h32") (pintype "bidirectional"))
      (node (ref "J21") (pin "h33") (pinfunction "h33_h33") (pintype "bidirectional"))
      (node (ref "J21") (pin "h35") (pinfunction "h35_h35") (pintype "bidirectional"))
      (node (ref "J21") (pin "h37") (pinfunction "h37_h37") (pintype "bidirectional"))
      (node (ref "J21") (pin "h39") (pinfunction "h39_h39") (pintype "bidirectional"))
      (node (ref "J21") (pin "h4") (pinfunction "h4_h4") (pintype "bidirectional"))
      (node (ref "J21") (pin "h5") (pinfunction "h5_h5") (pintype "bidirectional"))
      (node (ref "J21") (pin "h6") (pinfunction "h6_h6") (pintype "bidirectional"))
      (node (ref "J21") (pin "h7") (pinfunction "h7_h7") (pintype "bidirectional"))
      (node (ref "J21") (pin "h8") (pinfunction "h8_h8") (pintype "bidirectional"))
      (node (ref "J21") (pin "h9") (pinfunction "h9_h9") (pintype "bidirectional"))
    )
    (net (code "48") (name "P1V8") (class "Default")
      (node (ref "C776") (pin "2") (pinfunction "2_2") (pintype "passive"))
      (node (ref "C932") (pin "1") (pinfunction "1_1") (pintype "passive"))
      (node (ref "J21") (pin "a35") (pinfunction "a35_a35") (pintype "bidirectional"))
      (node (ref "J21") (pin "c35") (pinfunction "c35_c35") (pintype "bidirectional"))
    )
    (net (code "49") (name "P3V3") (class "Default")
      (node (ref "C993") (pin "2") (pinfunction "2_2") (pintype "passive"))
      (node (ref "C994") (pin "1") (pinfunction "1_1") (pintype "passive"))
      (node (ref "C995") (pin "1") (pinfunction "1_1") (pintype "passive"))
      (node (ref "J21") (pin "a34") (pinfunction "a34_a34") (pintype "bidirectional"))
      (node (ref "J21") (pin "b34") (pinfunction "b34_b34") (pintype "bidirectional"))
      (node (ref "J21") (pin "c34") (pinfunction "c34_c34") (pintype "bidirectional"))
      (node (ref "J21") (pin "d34") (pinfunction "d34_d34") (pintype "bidirectional"))
      (node (ref "J21") (pin "e34") (pinfunction "e34_e34") (pintype "bidirectional"))
      (node (ref "J21") (pin "f34") (pinfunction "f34_f34") (pintype "bidirectional"))
      (node (ref "J21") (pin "g34") (pinfunction "g34_g34") (pintype "bidirectional"))
      (node (ref "J21") (pin "h34") (pinfunction "h34_h34") (pintype "bidirectional"))
    )
    (net (code "50") (name "P12V0") (class "Default")
      (node (ref "C935") (pin "2") (pinfunction "2_2") (pintype "passive"))
      (node (ref "C947") (pin "1") (pinfunction "1_1") (pintype "passive"))
      (node (ref "C992") (pin "1") (pinfunction "1_1") (pintype "passive"))
      (node (ref "J21") (pin "a1") (pinfunction "a1_a1") (pintype "bidirectional"))
      (node (ref "J21") (pin "b1") (pinfunction "b1_b1") (pintype "bidirectional"))
      (node (ref "J21") (pin "c1") (pinfunction "c1_c1") (pintype "bidirectional"))
      (node (ref "J21") (pin "d1") (pinfunction "d1_d1") (pintype "bidirectional"))
      (node (ref "J21") (pin "e1") (pinfunction "e1_e1") (pintype "bidirectional"))
    )
    (net (code "51") (name "unconnected-(J21-Padb7)") (class "Default")
      (node (ref "J21") (pin "b7") (pinfunction "b7_b7") (pintype "bidirectional+no_connect"))
    )
    (net (code "52") (name "unconnected-(J21-Padb22)") (class "Default")
      (node (ref "J21") (pin "b22") (pinfunction "b22_b22") (pintype "bidirectional+no_connect"))
    )
    (net (code "53") (name "unconnected-(J21-Padb25)") (class "Default")
      (node (ref "J21") (pin "b25") (pinfunction "b25_b25") (pintype "bidirectional+no_connect"))
    )
    (net (code "54") (name "unconnected-(J21-Padb28)") (class "Default")
      (node (ref "J21") (pin "b28") (pinfunction "b28_b28") (pintype "bidirectional+no_connect"))
    )
    (net (code "55") (name "unconnected-(J21-Padb31)") (class "Default")
      (node (ref "J21") (pin "b31") (pinfunction "b31_b31") (pintype "bidirectional+no_connect"))
    )
    (net (code "56") (name "unconnected-(J21-Padc7)") (class "Default")
      (node (ref "J21") (pin "c7") (pinfunction "c7_c7") (pintype "bidirectional+no_connect"))
    )
    (net (code "57") (name "unconnected-(J21-Padc22)") (class "Default")
      (node (ref "J21") (pin "c22") (pinfunction "c22_c22") (pintype "bidirectional+no_connect"))
    )
    (net (code "58") (name "unconnected-(J21-Padc25)") (class "Default")
      (node (ref "J21") (pin "c25") (pinfunction "c25_c25") (pintype "bidirectional+no_connect"))
    )
    (net (code "59") (name "unconnected-(J21-Padc28)") (class "Default")
      (node (ref "J21") (pin "c28") (pinfunction "c28_c28") (pintype "bidirectional+no_connect"))
    )
    (net (code "60") (name "unconnected-(J21-Padc31)") (class "Default")
      (node (ref "J21") (pin "c31") (pinfunction "c31_c31") (pintype "bidirectional+no_connect"))
    )
    (net (code "61") (name "unconnected-(J21-Pade35)") (class "Default")
      (node (ref "J21") (pin "e35") (pinfunction "e35_e35") (pintype "bidirectional+no_connect"))
    )
    (net (code "62") (name "unconnected-(J21-Padf8)") (class "Default")
      (node (ref "J21") (pin "f8") (pinfunction "f8_f8") (pintype "bidirectional+no_connect"))
    )
    (net (code "63") (name "unconnected-(J21-Padf23)") (class "Default")
      (node (ref "J21") (pin "f23") (pinfunction "f23_f23") (pintype "bidirectional+no_connect"))
    )
    (net (code "64") (name "unconnected-(J21-Padf26)") (class "Default")
      (node (ref "J21") (pin "f26") (pinfunction "f26_f26") (pintype "bidirectional+no_connect"))
    )
    (net (code "65") (name "unconnected-(J21-Padf29)") (class "Default")
      (node (ref "J21") (pin "f29") (pinfunction "f29_f29") (pintype "bidirectional+no_connect"))
    )
    (net (code "66") (name "unconnected-(J21-Padf32)") (class "Default")
      (node (ref "J21") (pin "f32") (pinfunction "f32_f32") (pintype "bidirectional+no_connect"))
    )
    (net (code "67") (name "unconnected-(J21-Padg8)") (class "Default")
      (node (ref "J21") (pin "g8") (pinfunction "g8_g8") (pintype "bidirectional+no_connect"))
    )
    (net (code "68") (name "unconnected-(J21-Padg23)") (class "Default")
      (node (ref "J21") (pin "g23") (pinfunction "g23_g23") (pintype "bidirectional+no_connect"))
    )
    (net (code "69") (name "unconnected-(J21-Padg26)") (class "Default")
      (node (ref "J21") (pin "g26") (pinfunction "g26_g26") (pintype "bidirectional+no_connect"))
    )
    (net (code "70") (name "unconnected-(J21-Padg29)") (class "Default")
      (node (ref "J21") (pin "g29") (pinfunction "g29_g29") (pintype "bidirectional+no_connect"))
    )
    (net (code "71") (name "unconnected-(J21-Padg32)") (class "Default")
      (node (ref "J21") (pin "g32") (pinfunction "g32_g32") (pintype "bidirectional+no_connect"))
    )
    (net (code "72") (name "unconnected-(J21-Padg35)") (class "Default")
      (node (ref "J21") (pin "g35") (pinfunction "g35_g35") (pintype "bidirectional+no_connect"))
    )
  )
)
